# PIC.net
KiCad netlist of a schematic drawn in Altium Designer
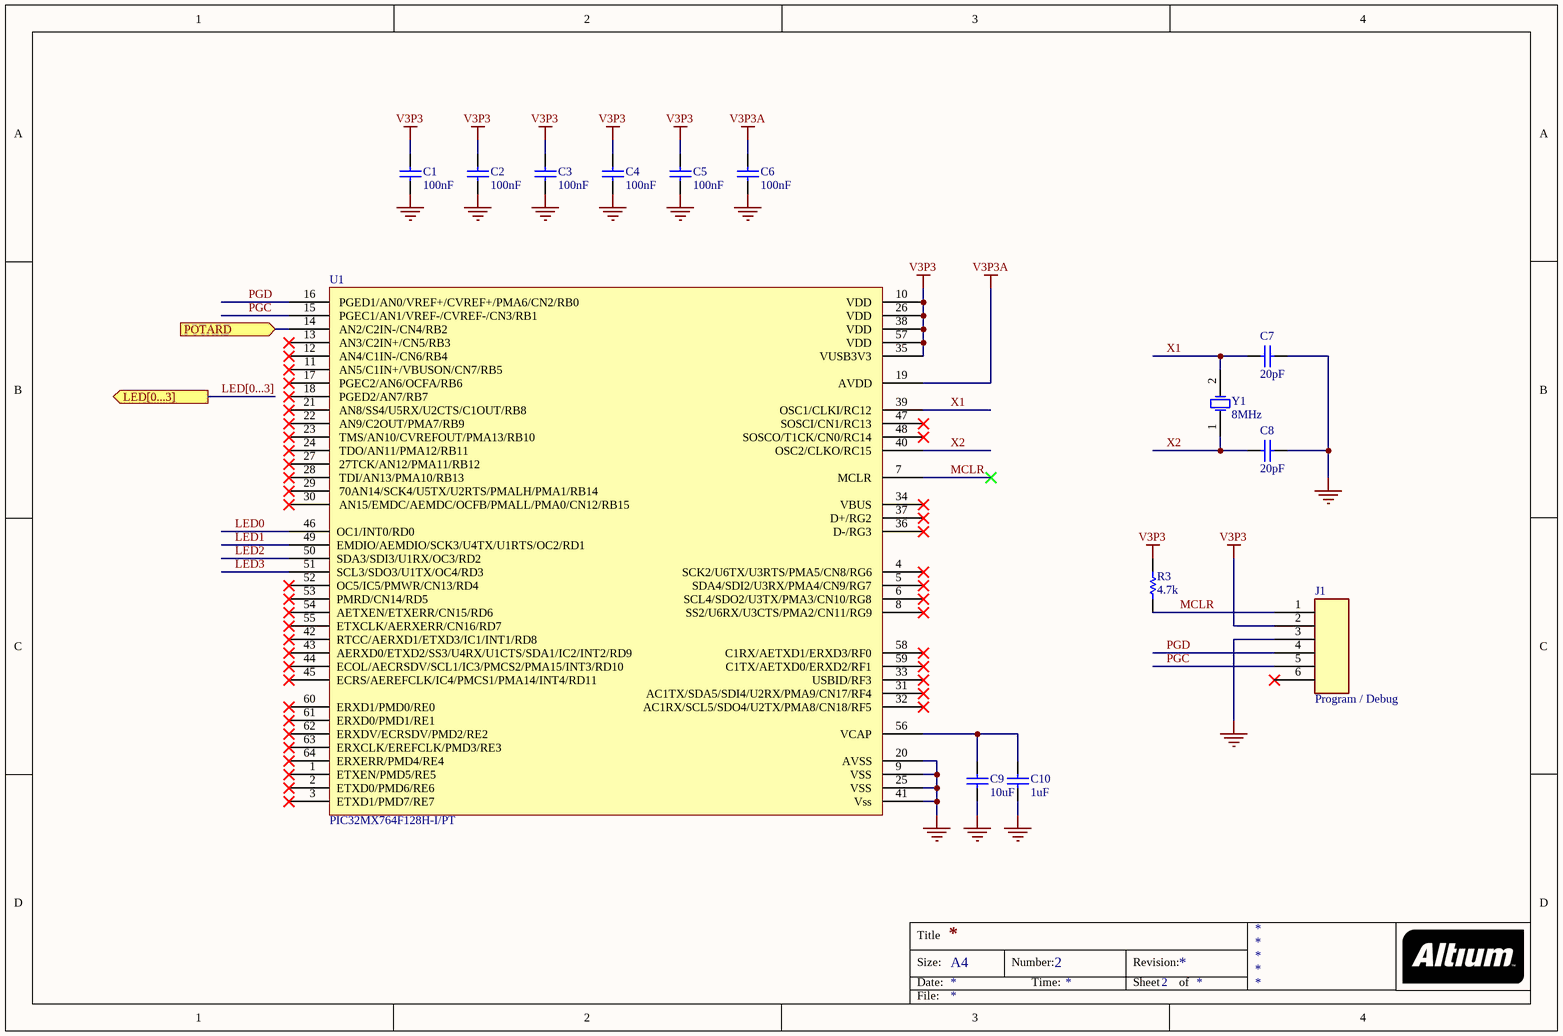
[diagram p0: PIC.SchDoc]

(export (version "E")
  (design (tool "Eeschema 10.0.6"))
  (components
    (comp (ref "C1")
      (value "100nF")
      (footprint "CAPC1608N")
      (description "Capacitor")
      (fields (field (name "PUBLISHER") "Altium Limited"))
      (libsource (lib "Miscellaneous Devices") (part "Cap"))
    )
    (comp (ref "C2")
      (value "100nF")
      (footprint "CAPC1608N")
      (description "Capacitor")
      (fields (field (name "PUBLISHER") "Altium Limited"))
      (libsource (lib "Miscellaneous Devices") (part "Cap"))
    )
    (comp (ref "C3")
      (value "100nF")
      (footprint "CAPC1608N")
      (description "Capacitor")
      (fields (field (name "PUBLISHER") "Altium Limited"))
      (libsource (lib "Miscellaneous Devices") (part "Cap"))
    )
    (comp (ref "C4")
      (value "100nF")
      (footprint "CAPC1608N")
      (description "Capacitor")
      (fields (field (name "PUBLISHER") "Altium Limited"))
      (libsource (lib "Miscellaneous Devices") (part "Cap"))
    )
    (comp (ref "C5")
      (value "100nF")
      (footprint "CAPC1608N")
      (description "Capacitor")
      (fields (field (name "PUBLISHER") "Altium Limited"))
      (libsource (lib "Miscellaneous Devices") (part "Cap"))
    )
    (comp (ref "C6")
      (value "100nF")
      (footprint "CAPC1608N")
      (description "Capacitor")
      (fields (field (name "PUBLISHER") "Altium Limited"))
      (libsource (lib "Miscellaneous Devices") (part "Cap"))
    )
    (comp (ref "C7")
      (value "20pF")
      (footprint "CAPC1608N")
      (description "Capacitor")
      (fields (field (name "PUBLISHER") "Altium Limited"))
      (libsource (lib "Miscellaneous Devices") (part "Cap"))
    )
    (comp (ref "C8")
      (value "20pF")
      (footprint "CAPC1608N")
      (description "Capacitor")
      (fields (field (name "PUBLISHER") "Altium Limited"))
      (libsource (lib "Miscellaneous Devices") (part "Cap"))
    )
    (comp (ref "C9")
      (value "10uF")
      (footprint "CAPC2012N")
      (description "Capacitor")
      (fields (field (name "PUBLISHER") "Altium Limited"))
      (libsource (lib "Miscellaneous Devices") (part "Cap"))
    )
    (comp (ref "C10")
      (value "1uF")
      (footprint "CAPC1608N")
      (description "Capacitor")
      (fields (field (name "PUBLISHER") "Altium Limited"))
      (libsource (lib "Miscellaneous Devices") (part "Cap"))
    )
    (comp (ref "J1")
      (value "Program / Debug")
      (footprint "RJ12_90")
      (description "RJ11")
      (fields (field (name "NAME") "J1") (field (name "TYPE") "Program / Debug"))
      (libsource (lib "TP02_SCHLib") (part "Program / Debug"))
    )
    (comp (ref "R3")
      (value "4.7k")
      (footprint "RESC1608N")
      (description "Resistor")
      (fields (field (name "PUBLISHER") "Altium Limited"))
      (libsource (lib "Miscellaneous Devices") (part "Res1"))
    )
    (comp (ref "U1")
      (value "PIC32MX764F128H-I/PT")
      (footprint "QFP50P1200X1200X120-64")
      (description "PIC32MX764F128H")
      (libsource (lib "TP02_SCHLib") (part "PIC"))
    )
    (comp (ref "Y1")
      (value "8MHz")
      (footprint "HC49/4H SMX CRYSTAL")
      (description "Crystal Oscillator")
      (fields (field (name "PUBLISHER") "Altium Limited"))
      (libsource (lib "Miscellaneous Devices") (part "XTAL"))
    )
  )
  (nets
    (net (code "2") (name "/LED0") (class "Default")
      (node (ref "U1") (pin "46") (pinfunction "OC1/INT0/RD0_46") (pintype "passive"))
    )
    (net (code "3") (name "/LED1") (class "Default")
      (node (ref "U1") (pin "49") (pinfunction "EMDIO/AEMDIO/SCK3/U4TX/U1RTS/OC2/RD1_49") (pintype "passive"))
    )
    (net (code "4") (name "/LED2") (class "Default")
      (node (ref "U1") (pin "50") (pinfunction "SDA3/SDI3/U1RX/OC3/RD2_50") (pintype "passive"))
    )
    (net (code "5") (name "/LED3") (class "Default")
      (node (ref "U1") (pin "51") (pinfunction "SCL3/SDO3/U1TX/OC4/RD3_51") (pintype "passive"))
    )
    (net (code "6") (name "/MCLR") (class "Default")
      (node (ref "J1") (pin "1") (pintype "passive"))
      (node (ref "R3") (pin "1") (pinfunction "1_1") (pintype "passive"))
      (node (ref "U1") (pin "7") (pinfunction "MCLR_7") (pintype "passive"))
    )
    (net (code "7") (name "/PGC") (class "Default")
      (node (ref "J1") (pin "5") (pinfunction "68_5") (pintype "passive"))
      (node (ref "U1") (pin "15") (pinfunction "PGEC1/AN1/VREF-/CVREF-/CN3/RB1_15") (pintype "passive"))
    )
    (net (code "8") (name "/PGD") (class "Default")
      (node (ref "J1") (pin "4") (pinfunction "67_4") (pintype "passive"))
      (node (ref "U1") (pin "16") (pinfunction "PGED1/AN0/VREF+/CVREF+/PMA6/CN2/RB0_16") (pintype "passive"))
    )
    (net (code "9") (name "/POTARD") (class "Default")
      (node (ref "U1") (pin "14") (pinfunction "AN2/C2IN-/CN4/RB2_14") (pintype "passive"))
    )
    (net (code "10") (name "/X1") (class "Default")
      (node (ref "C7") (pin "2") (pinfunction "2_2") (pintype "passive"))
      (node (ref "U1") (pin "39") (pinfunction "OSC1/CLKI/RC12_39") (pintype "passive"))
      (node (ref "Y1") (pin "2") (pinfunction "OSC2_2") (pintype "passive"))
    )
    (net (code "11") (name "/X2") (class "Default")
      (node (ref "C8") (pin "1") (pinfunction "1_1") (pintype "passive"))
      (node (ref "U1") (pin "40") (pinfunction "OSC2/CLKO/RC15_40") (pintype "passive"))
      (node (ref "Y1") (pin "1") (pinfunction "OSC1_1") (pintype "passive"))
    )
    (net (code "13") (name "GND") (class "Default")
      (node (ref "C1") (pin "1") (pinfunction "1_1") (pintype "passive"))
      (node (ref "C10") (pin "2") (pinfunction "2_2") (pintype "passive"))
      (node (ref "C2") (pin "1") (pinfunction "1_1") (pintype "passive"))
      (node (ref "C3") (pin "1") (pinfunction "1_1") (pintype "passive"))
      (node (ref "C4") (pin "1") (pinfunction "1_1") (pintype "passive"))
      (node (ref "C5") (pin "1") (pinfunction "1_1") (pintype "passive"))
      (node (ref "C6") (pin "1") (pinfunction "1_1") (pintype "passive"))
      (node (ref "C7") (pin "1") (pinfunction "1_1") (pintype "passive"))
      (node (ref "C8") (pin "2") (pinfunction "2_2") (pintype "passive"))
      (node (ref "C9") (pin "1") (pinfunction "1_1") (pintype "passive"))
      (node (ref "J1") (pin "3") (pintype "passive"))
      (node (ref "U1") (pin "20") (pinfunction "AVSS_20") (pintype "passive"))
      (node (ref "U1") (pin "25") (pinfunction "VSS_25") (pintype "passive"))
      (node (ref "U1") (pin "41") (pinfunction "Vss_41") (pintype "passive"))
      (node (ref "U1") (pin "9") (pinfunction "VSS_9") (pintype "passive"))
    )
    (net (code "14") (name "Net-(U1-VCAP)") (class "Default")
      (node (ref "C10") (pin "1") (pinfunction "1_1") (pintype "passive"))
      (node (ref "C9") (pin "2") (pinfunction "2_2") (pintype "passive"))
      (node (ref "U1") (pin "56") (pinfunction "VCAP_56") (pintype "passive"))
    )
    (net (code "15") (name "V3P3") (class "Default")
      (node (ref "C1") (pin "2") (pinfunction "2_2") (pintype "passive"))
      (node (ref "C2") (pin "2") (pinfunction "2_2") (pintype "passive"))
      (node (ref "C3") (pin "2") (pinfunction "2_2") (pintype "passive"))
      (node (ref "C4") (pin "2") (pinfunction "2_2") (pintype "passive"))
      (node (ref "C5") (pin "2") (pinfunction "2_2") (pintype "passive"))
      (node (ref "J1") (pin "2") (pinfunction "65_2") (pintype "passive"))
      (node (ref "R3") (pin "2") (pinfunction "2_2") (pintype "passive"))
      (node (ref "U1") (pin "10") (pinfunction "VDD_10") (pintype "passive"))
      (node (ref "U1") (pin "26") (pinfunction "VDD_26") (pintype "passive"))
      (node (ref "U1") (pin "35") (pinfunction "VUSB3V3_35") (pintype "passive"))
      (node (ref "U1") (pin "38") (pinfunction "VDD_38") (pintype "passive"))
      (node (ref "U1") (pin "57") (pinfunction "VDD_57") (pintype "passive"))
    )
    (net (code "16") (name "V3P3A") (class "Default")
      (node (ref "C6") (pin "2") (pinfunction "2_2") (pintype "passive"))
      (node (ref "U1") (pin "19") (pinfunction "AVDD_19") (pintype "passive"))
    )
    (net (code "17") (name "unconnected-(J1-69-Pad6)") (class "Default")
      (node (ref "J1") (pin "6") (pinfunction "69_6") (pintype "power_in+no_connect"))
    )
    (net (code "18") (name "unconnected-(U1-27TCK{slash}AN12{slash}PMA11{slash}RB12-Pad27)") (class "Default")
      (node (ref "U1") (pin "27") (pinfunction "27TCK/AN12/PMA11/RB12_27") (pintype "passive+no_connect"))
    )
    (net (code "19") (name "unconnected-(U1-70AN14{slash}SCK4{slash}U5TX{slash}U2RTS{slash}PMALH{slash}PMA1{slash}RB14-Pad29)") (class "Default")
      (node (ref "U1") (pin "29") (pinfunction "70AN14/SCK4/U5TX/U2RTS/PMALH/PMA1/RB14_29") (pintype "passive+no_connect"))
    )
    (net (code "20") (name "unconnected-(U1-AC1RX{slash}SCL5{slash}SDO4{slash}U2TX{slash}PMA8{slash}CN18{slash}RF5-Pad32)") (class "Default")
      (node (ref "U1") (pin "32") (pinfunction "AC1RX/SCL5/SDO4/U2TX/PMA8/CN18/RF5_32") (pintype "passive+no_connect"))
    )
    (net (code "21") (name "unconnected-(U1-AC1TX{slash}SDA5{slash}SDI4{slash}U2RX{slash}PMA9{slash}CN17{slash}RF4-Pad31)") (class "Default")
      (node (ref "U1") (pin "31") (pinfunction "AC1TX/SDA5/SDI4/U2RX/PMA9/CN17/RF4_31") (pintype "passive+no_connect"))
    )
    (net (code "22") (name "unconnected-(U1-AERXD0{slash}ETXD2{slash}SS3{slash}U4RX{slash}U1CTS{slash}SDA1{slash}IC2{slash}INT2{slash}RD9-Pad43)") (class "Default")
      (node (ref "U1") (pin "43") (pinfunction "AERXD0/ETXD2/SS3/U4RX/U1CTS/SDA1/IC2/INT2/RD9_43") (pintype "passive+no_connect"))
    )
    (net (code "23") (name "unconnected-(U1-AETXEN{slash}ETXERR{slash}CN15{slash}RD6-Pad54)") (class "Default")
      (node (ref "U1") (pin "54") (pinfunction "AETXEN/ETXERR/CN15/RD6_54") (pintype "passive+no_connect"))
    )
    (net (code "24") (name "unconnected-(U1-AN3{slash}C2IN+{slash}CN5{slash}RB3-Pad13)") (class "Default")
      (node (ref "U1") (pin "13") (pinfunction "AN3/C2IN+/CN5/RB3_13") (pintype "passive+no_connect"))
    )
    (net (code "25") (name "unconnected-(U1-AN4{slash}C1IN-{slash}CN6{slash}RB4-Pad12)") (class "Default")
      (node (ref "U1") (pin "12") (pinfunction "AN4/C1IN-/CN6/RB4_12") (pintype "passive+no_connect"))
    )
    (net (code "26") (name "unconnected-(U1-AN5{slash}C1IN+{slash}VBUSON{slash}CN7{slash}RB5-Pad11)") (class "Default")
      (node (ref "U1") (pin "11") (pinfunction "AN5/C1IN+/VBUSON/CN7/RB5_11") (pintype "passive+no_connect"))
    )
    (net (code "27") (name "unconnected-(U1-AN8{slash}SS4{slash}U5RX{slash}U2CTS{slash}C1OUT{slash}RB8-Pad21)") (class "Default")
      (node (ref "U1") (pin "21") (pinfunction "AN8/SS4/U5RX/U2CTS/C1OUT/RB8_21") (pintype "passive+no_connect"))
    )
    (net (code "28") (name "unconnected-(U1-AN9{slash}C2OUT{slash}PMA7{slash}RB9-Pad22)") (class "Default")
      (node (ref "U1") (pin "22") (pinfunction "AN9/C2OUT/PMA7/RB9_22") (pintype "passive+no_connect"))
    )
    (net (code "29") (name "unconnected-(U1-AN15{slash}EMDC{slash}AEMDC{slash}OCFB{slash}PMALL{slash}PMA0{slash}CN12{slash}RB15-Pad30)") (class "Default")
      (node (ref "U1") (pin "30") (pinfunction "AN15/EMDC/AEMDC/OCFB/PMALL/PMA0/CN12/RB15_30") (pintype "passive+no_connect"))
    )
    (net (code "30") (name "unconnected-(U1-C1RX{slash}AETXD1{slash}ERXD3{slash}RF0-Pad58)") (class "Default")
      (node (ref "U1") (pin "58") (pinfunction "C1RX/AETXD1/ERXD3/RF0_58") (pintype "passive+no_connect"))
    )
    (net (code "31") (name "unconnected-(U1-C1TX{slash}AETXD0{slash}ERXD2{slash}RF1-Pad59)") (class "Default")
      (node (ref "U1") (pin "59") (pinfunction "C1TX/AETXD0/ERXD2/RF1_59") (pintype "passive+no_connect"))
    )
    (net (code "32") (name "unconnected-(U1-D+{slash}RG2-Pad37)") (class "Default")
      (node (ref "U1") (pin "37") (pinfunction "D+/RG2_37") (pintype "passive+no_connect"))
    )
    (net (code "33") (name "unconnected-(U1-D-{slash}RG3-Pad36)") (class "Default")
      (node (ref "U1") (pin "36") (pinfunction "D-/RG3_36") (pintype "passive+no_connect"))
    )
    (net (code "34") (name "unconnected-(U1-ECOL{slash}AECRSDV{slash}SCL1{slash}IC3{slash}PMCS2{slash}PMA15{slash}INT3{slash}RD10-Pad44)") (class "Default")
      (node (ref "U1") (pin "44") (pinfunction "ECOL/AECRSDV/SCL1/IC3/PMCS2/PMA15/INT3/RD10_44") (pintype "passive+no_connect"))
    )
    (net (code "35") (name "unconnected-(U1-ECRS{slash}AEREFCLK{slash}IC4{slash}PMCS1{slash}PMA14{slash}INT4{slash}RD11-Pad45)") (class "Default")
      (node (ref "U1") (pin "45") (pinfunction "ECRS/AEREFCLK/IC4/PMCS1/PMA14/INT4/RD11_45") (pintype "passive+no_connect"))
    )
    (net (code "36") (name "unconnected-(U1-ERXCLK{slash}EREFCLK{slash}PMD3{slash}RE3-Pad63)") (class "Default")
      (node (ref "U1") (pin "63") (pinfunction "ERXCLK/EREFCLK/PMD3/RE3_63") (pintype "passive+no_connect"))
    )
    (net (code "37") (name "unconnected-(U1-ERXD0{slash}PMD1{slash}RE1-Pad61)") (class "Default")
      (node (ref "U1") (pin "61") (pinfunction "ERXD0/PMD1/RE1_61") (pintype "passive+no_connect"))
    )
    (net (code "38") (name "unconnected-(U1-ERXD1{slash}PMD0{slash}RE0-Pad60)") (class "Default")
      (node (ref "U1") (pin "60") (pinfunction "ERXD1/PMD0/RE0_60") (pintype "passive+no_connect"))
    )
    (net (code "39") (name "unconnected-(U1-ERXDV{slash}ECRSDV{slash}PMD2{slash}RE2-Pad62)") (class "Default")
      (node (ref "U1") (pin "62") (pinfunction "ERXDV/ECRSDV/PMD2/RE2_62") (pintype "passive+no_connect"))
    )
    (net (code "40") (name "unconnected-(U1-ERXERR{slash}PMD4{slash}RE4-Pad64)") (class "Default")
      (node (ref "U1") (pin "64") (pinfunction "ERXERR/PMD4/RE4_64") (pintype "passive+no_connect"))
    )
    (net (code "41") (name "unconnected-(U1-ETXCLK{slash}AERXERR{slash}CN16{slash}RD7-Pad55)") (class "Default")
      (node (ref "U1") (pin "55") (pinfunction "ETXCLK/AERXERR/CN16/RD7_55") (pintype "passive+no_connect"))
    )
    (net (code "42") (name "unconnected-(U1-ETXD0{slash}PMD6{slash}RE6-Pad2)") (class "Default")
      (node (ref "U1") (pin "2") (pinfunction "ETXD0/PMD6/RE6_2") (pintype "passive+no_connect"))
    )
    (net (code "43") (name "unconnected-(U1-ETXD1{slash}PMD7{slash}RE7-Pad3)") (class "Default")
      (node (ref "U1") (pin "3") (pinfunction "ETXD1/PMD7/RE7_3") (pintype "passive+no_connect"))
    )
    (net (code "44") (name "unconnected-(U1-ETXEN{slash}PMD5{slash}RE5-Pad1)") (class "Default")
      (node (ref "U1") (pin "1") (pinfunction "ETXEN/PMD5/RE5_1") (pintype "passive+no_connect"))
    )
    (net (code "45") (name "unconnected-(U1-OC5{slash}IC5{slash}PMWR{slash}CN13{slash}RD4-Pad52)") (class "Default")
      (node (ref "U1") (pin "52") (pinfunction "OC5/IC5/PMWR/CN13/RD4_52") (pintype "passive+no_connect"))
    )
    (net (code "46") (name "unconnected-(U1-PGEC2{slash}AN6{slash}OCFA{slash}RB6-Pad17)") (class "Default")
      (node (ref "U1") (pin "17") (pinfunction "PGEC2/AN6/OCFA/RB6_17") (pintype "passive+no_connect"))
    )
    (net (code "47") (name "unconnected-(U1-PGED2{slash}AN7{slash}RB7-Pad18)") (class "Default")
      (node (ref "U1") (pin "18") (pinfunction "PGED2/AN7/RB7_18") (pintype "passive+no_connect"))
    )
    (net (code "48") (name "unconnected-(U1-PMRD{slash}CN14{slash}RD5-Pad53)") (class "Default")
      (node (ref "U1") (pin "53") (pinfunction "PMRD/CN14/RD5_53") (pintype "passive+no_connect"))
    )
    (net (code "49") (name "unconnected-(U1-RTCC{slash}AERXD1{slash}ETXD3{slash}IC1{slash}INT1{slash}RD8-Pad42)") (class "Default")
      (node (ref "U1") (pin "42") (pinfunction "RTCC/AERXD1/ETXD3/IC1/INT1/RD8_42") (pintype "passive+no_connect"))
    )
    (net (code "50") (name "unconnected-(U1-SCK2{slash}U6TX{slash}U3RTS{slash}PMA5{slash}CN8{slash}RG6-Pad4)") (class "Default")
      (node (ref "U1") (pin "4") (pinfunction "SCK2/U6TX/U3RTS/PMA5/CN8/RG6_4") (pintype "passive+no_connect"))
    )
    (net (code "51") (name "unconnected-(U1-SCL4{slash}SDO2{slash}U3TX{slash}PMA3{slash}CN10{slash}RG8-Pad6)") (class "Default")
      (node (ref "U1") (pin "6") (pinfunction "SCL4/SDO2/U3TX/PMA3/CN10/RG8_6") (pintype "passive+no_connect"))
    )
    (net (code "52") (name "unconnected-(U1-SDA4{slash}SDI2{slash}U3RX{slash}PMA4{slash}CN9{slash}RG7-Pad5)") (class "Default")
      (node (ref "U1") (pin "5") (pinfunction "SDA4/SDI2/U3RX/PMA4/CN9/RG7_5") (pintype "passive+no_connect"))
    )
    (net (code "53") (name "unconnected-(U1-SOSCI{slash}CN1{slash}RC13-Pad47)") (class "Default")
      (node (ref "U1") (pin "47") (pinfunction "SOSCI/CN1/RC13_47") (pintype "passive+no_connect"))
    )
    (net (code "54") (name "unconnected-(U1-SOSCO{slash}T1CK{slash}CN0{slash}RC14-Pad48)") (class "Default")
      (node (ref "U1") (pin "48") (pinfunction "SOSCO/T1CK/CN0/RC14_48") (pintype "passive+no_connect"))
    )
    (net (code "55") (name "unconnected-(U1-SS2{slash}U6RX{slash}U3CTS{slash}PMA2{slash}CN11{slash}RG9-Pad8)") (class "Default")
      (node (ref "U1") (pin "8") (pinfunction "SS2/U6RX/U3CTS/PMA2/CN11/RG9_8") (pintype "passive+no_connect"))
    )
    (net (code "56") (name "unconnected-(U1-TDI{slash}AN13{slash}PMA10{slash}RB13-Pad28)") (class "Default")
      (node (ref "U1") (pin "28") (pinfunction "TDI/AN13/PMA10/RB13_28") (pintype "passive+no_connect"))
    )
    (net (code "57") (name "unconnected-(U1-TDO{slash}AN11{slash}PMA12{slash}RB11-Pad24)") (class "Default")
      (node (ref "U1") (pin "24") (pinfunction "TDO/AN11/PMA12/RB11_24") (pintype "passive+no_connect"))
    )
    (net (code "58") (name "unconnected-(U1-TMS{slash}AN10{slash}CVREFOUT{slash}PMA13{slash}RB10-Pad23)") (class "Default")
      (node (ref "U1") (pin "23") (pinfunction "TMS/AN10/CVREFOUT/PMA13/RB10_23") (pintype "passive+no_connect"))
    )
    (net (code "59") (name "unconnected-(U1-USBID{slash}RF3-Pad33)") (class "Default")
      (node (ref "U1") (pin "33") (pinfunction "USBID/RF3_33") (pintype "passive+no_connect"))
    )
    (net (code "60") (name "unconnected-(U1-VBUS-Pad34)") (class "Default")
      (node (ref "U1") (pin "34") (pinfunction "VBUS_34") (pintype "passive+no_connect"))
    )
  )
)
